# AFPGA_FMC2_bank2.net
KiCad netlist of a schematic drawn in Altium Designer
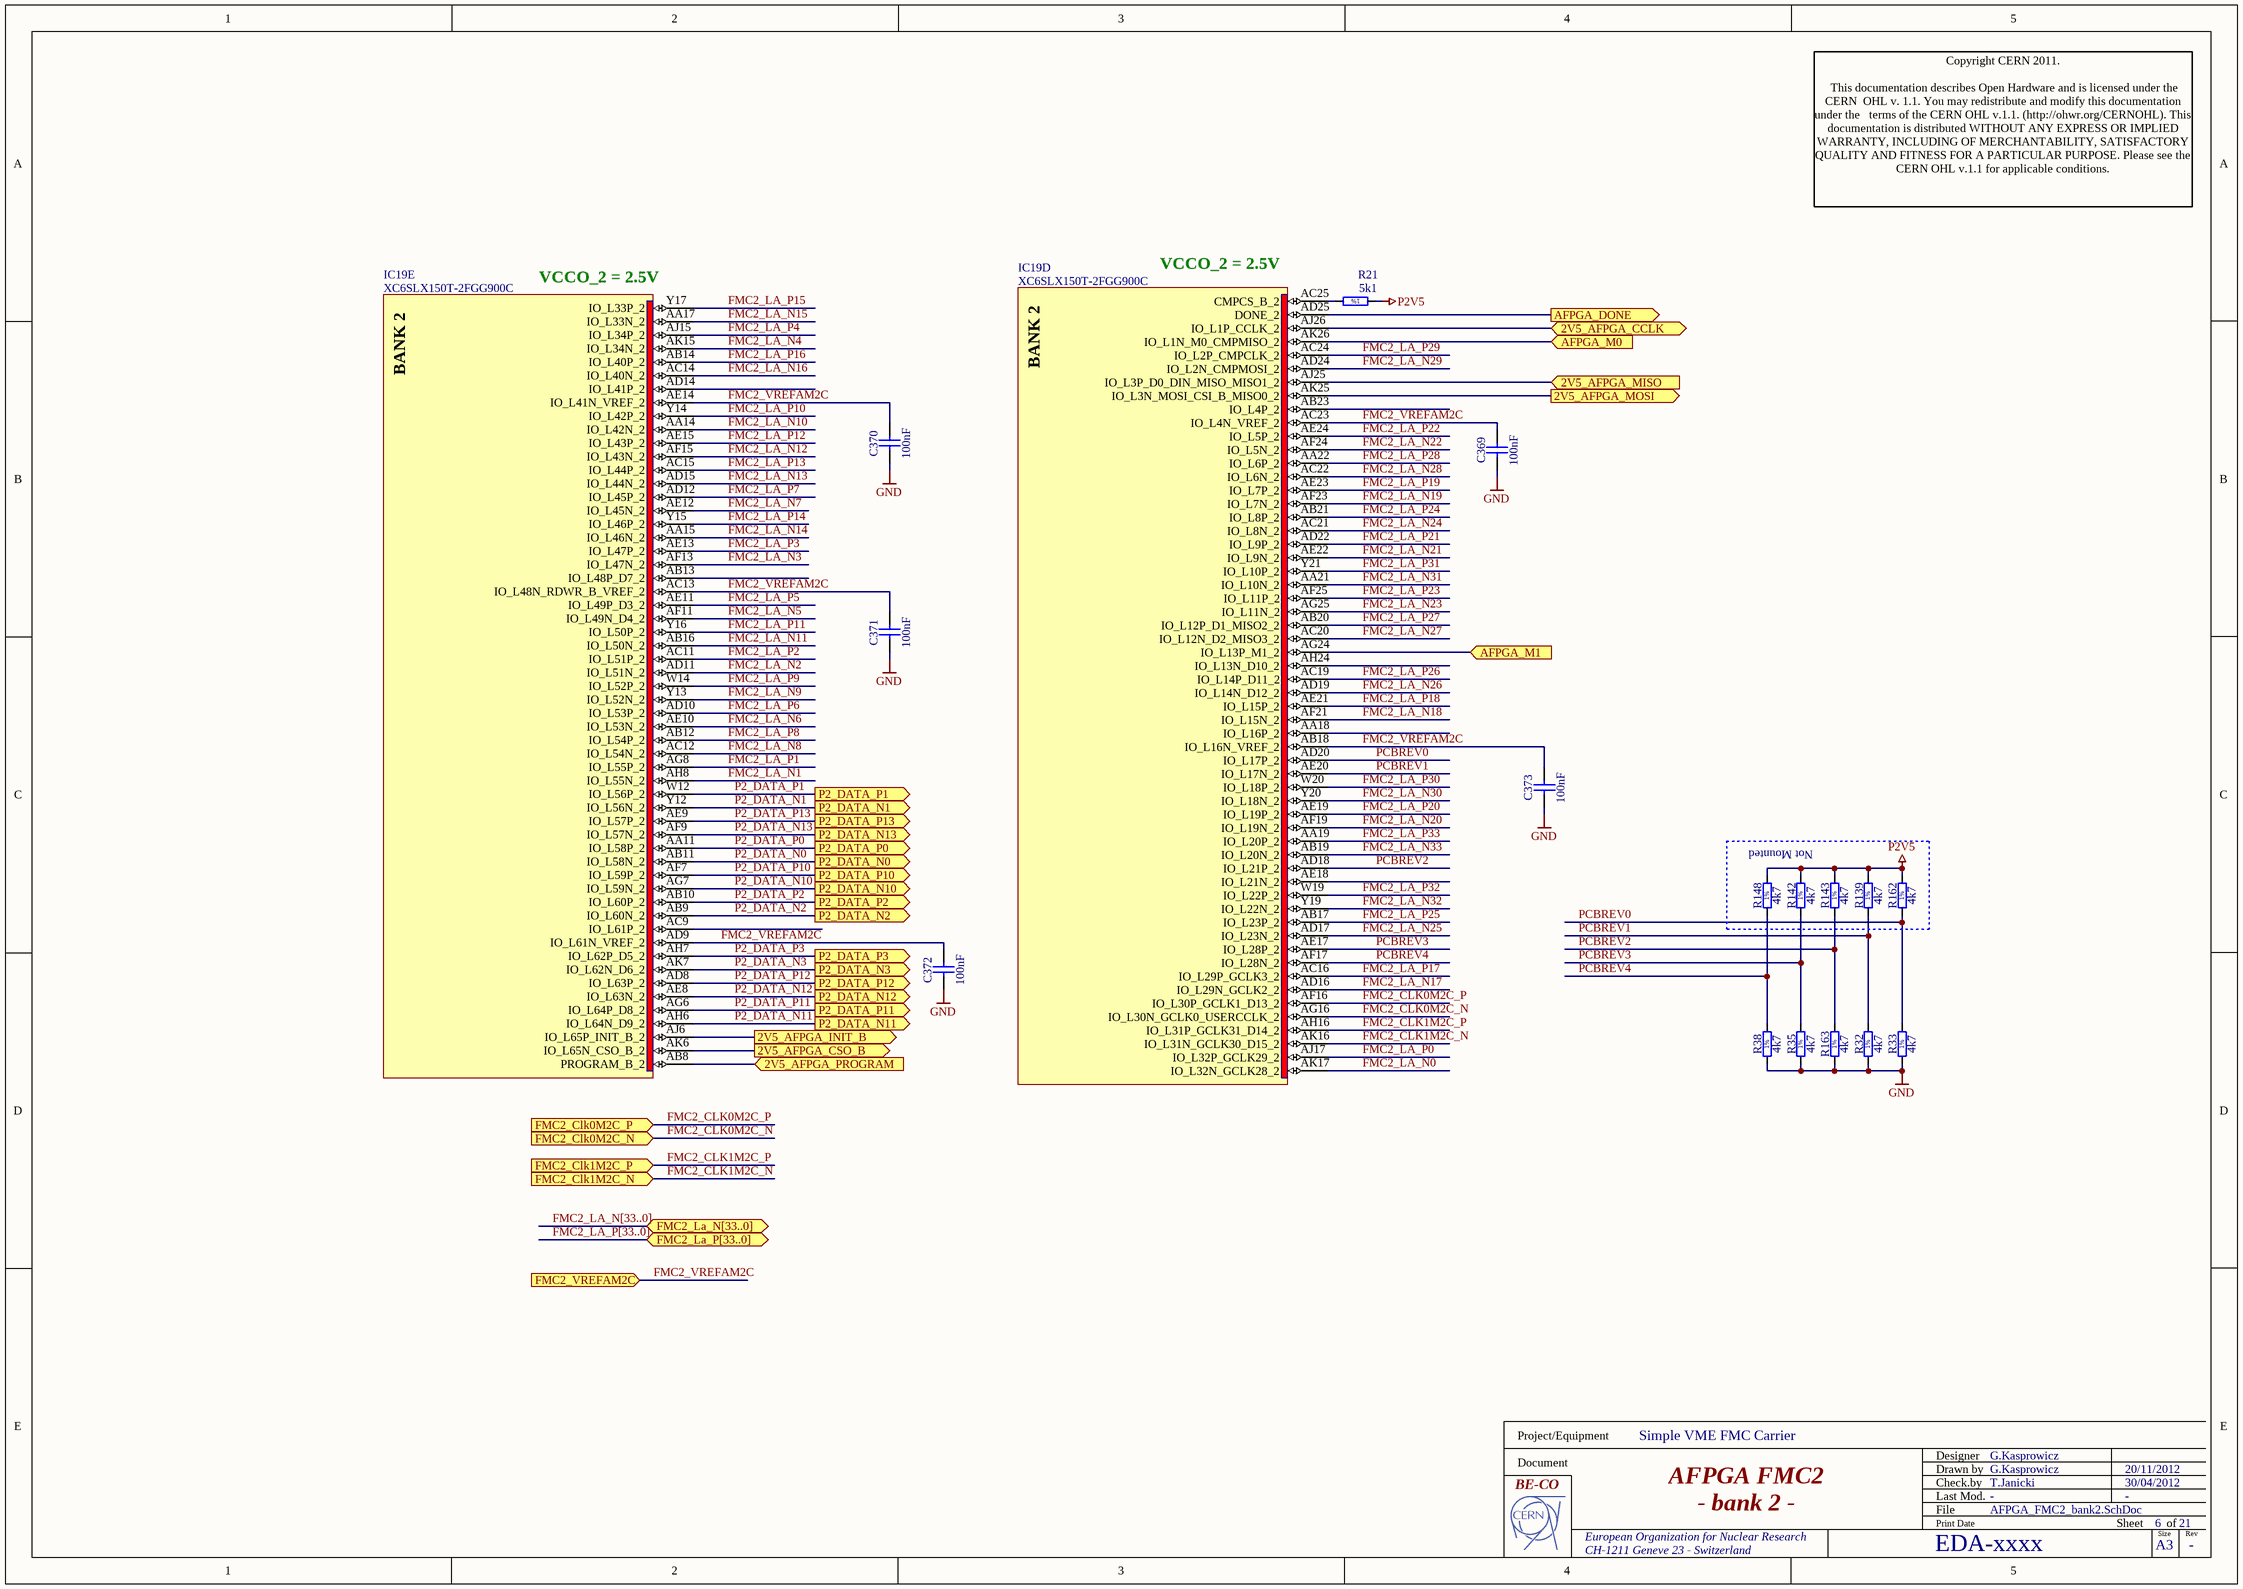
[diagram p0: AFPGA_FMC2_bank2.SchDoc]

(export (version "E")
  (design (tool "Eeschema 10.0.6"))
  (components
    (comp (ref "C369")
      (value "100nF")
      (footprint "CAPC1005X55N")
      (description "Non-polarised capacitor")
      (fields
        (field (name "PART NUMBER") "CC0402_100NF_16V_10%_X7R")
        (field (name "VOLTAGE") "16V")
        (field (name "AUTHOR") "CERN DEM JLC")
      )
      (libsource (lib "Capacitors") (part "Capacitor - non polarized"))
    )
    (comp (ref "C370")
      (value "100nF")
      (footprint "CAPC1005X55N")
      (description "Non-polarised capacitor")
      (fields
        (field (name "PART NUMBER") "CC0402_100NF_16V_10%_X7R")
        (field (name "VOLTAGE") "16V")
        (field (name "AUTHOR") "CERN DEM JLC")
      )
      (libsource (lib "Capacitors") (part "Capacitor - non polarized"))
    )
    (comp (ref "C371")
      (value "100nF")
      (footprint "CAPC1005X55N")
      (description "Non-polarised capacitor")
      (fields
        (field (name "PART NUMBER") "CC0402_100NF_16V_10%_X7R")
        (field (name "VOLTAGE") "16V")
        (field (name "AUTHOR") "CERN DEM JLC")
      )
      (libsource (lib "Capacitors") (part "Capacitor - non polarized"))
    )
    (comp (ref "C372")
      (value "100nF")
      (footprint "CAPC1005X55N")
      (description "Non-polarised capacitor")
      (fields
        (field (name "PART NUMBER") "CC0402_100NF_16V_10%_X7R")
        (field (name "VOLTAGE") "16V")
        (field (name "AUTHOR") "CERN DEM JLC")
      )
      (libsource (lib "Capacitors") (part "Capacitor - non polarized"))
    )
    (comp (ref "C373")
      (value "100nF")
      (footprint "CAPC1005X55N")
      (description "Non-polarised capacitor")
      (fields
        (field (name "PART NUMBER") "CC0402_100NF_16V_10%_X7R")
        (field (name "VOLTAGE") "16V")
        (field (name "AUTHOR") "CERN DEM JLC")
      )
      (libsource (lib "Capacitors") (part "Capacitor - non polarized"))
    )
    (comp (ref "IC19")
      (value "XC6SLX150T-2FGG900C")
      (footprint "BGA900C100P30X30_3100X3100X260")
      (description "SPARTAN-6, FPGA, 900-Ball BGA, Commercial Grade, Pb-Free")
      (fields (field (name "MANUFACTURER") "XILINX") (field (name "AUTHOR") "CERN DEM JLC"))
      (libsource (lib "ICs And Semiconductors") (part "XC6SLX150T-2FGG900C"))
    )
    (comp (ref "R21")
      (value "5k1")
      (footprint "RESC1608X55N")
      (description "Resistor - 1%")
      (fields
        (field (name "PART NUMBER") "R0603_5K1_1%_0.1W_100PPM")
        (field (name "POWER") "0.1W")
        (field (name "AUTHOR") "CERN DEM JLC")
      )
      (libsource (lib "Resistors") (part "Resistor - 1%"))
    )
    (comp (ref "R32")
      (value "4k7")
      (footprint "RESC1608X55N")
      (description "Resistor - 1%")
      (fields
        (field (name "PART NUMBER") "R0603_4K7_1%_0.1W_100PPM")
        (field (name "POWER") "0.1W")
        (field (name "AUTHOR") "CERN DEM JLC")
      )
      (libsource (lib "Resistors") (part "Resistor - 1%"))
    )
    (comp (ref "R33")
      (value "4k7")
      (footprint "RESC1608X55N")
      (description "Resistor - 1%")
      (fields
        (field (name "PART NUMBER") "R0603_4K7_1%_0.1W_100PPM")
        (field (name "POWER") "0.1W")
        (field (name "AUTHOR") "CERN DEM JLC")
      )
      (libsource (lib "Resistors") (part "Resistor - 1%"))
    )
    (comp (ref "R35")
      (value "4k7")
      (footprint "RESC1608X55N")
      (description "Resistor - 1%")
      (fields
        (field (name "PART NUMBER") "R0603_4K7_1%_0.1W_100PPM")
        (field (name "POWER") "0.1W")
        (field (name "AUTHOR") "CERN DEM JLC")
      )
      (libsource (lib "Resistors") (part "Resistor - 1%"))
    )
    (comp (ref "R38")
      (value "4k7")
      (footprint "RESC1608X55N")
      (description "Resistor - 1%")
      (fields
        (field (name "PART NUMBER") "R0603_4K7_1%_0.1W_100PPM")
        (field (name "POWER") "0.1W")
        (field (name "AUTHOR") "CERN DEM JLC")
      )
      (libsource (lib "Resistors") (part "Resistor - 1%"))
    )
    (comp (ref "R139")
      (value "4k7")
      (footprint "RESC1608X55N")
      (description "Resistor - 1%")
      (fields
        (field (name "PART NUMBER") "R0603_4K7_1%_0.1W_100PPM")
        (field (name "POWER") "0.1W")
        (field (name "AUTHOR") "CERN DEM JLC")
      )
      (libsource (lib "Resistors") (part "Resistor - 1%"))
    )
    (comp (ref "R142")
      (value "4k7")
      (footprint "RESC1608X55N")
      (description "Resistor - 1%")
      (fields
        (field (name "PART NUMBER") "R0603_4K7_1%_0.1W_100PPM")
        (field (name "POWER") "0.1W")
        (field (name "AUTHOR") "CERN DEM JLC")
      )
      (libsource (lib "Resistors") (part "Resistor - 1%"))
    )
    (comp (ref "R143")
      (value "4k7")
      (footprint "RESC1608X55N")
      (description "Resistor - 1%")
      (fields
        (field (name "PART NUMBER") "R0603_4K7_1%_0.1W_100PPM")
        (field (name "POWER") "0.1W")
        (field (name "AUTHOR") "CERN DEM JLC")
      )
      (libsource (lib "Resistors") (part "Resistor - 1%"))
    )
    (comp (ref "R148")
      (value "4k7")
      (footprint "RESC1608X55N")
      (description "Resistor - 1%")
      (fields
        (field (name "PART NUMBER") "R0603_4K7_1%_0.1W_100PPM")
        (field (name "POWER") "0.1W")
        (field (name "AUTHOR") "CERN DEM JLC")
      )
      (libsource (lib "Resistors") (part "Resistor - 1%"))
    )
    (comp (ref "R162")
      (value "4k7")
      (footprint "RESC1608X55N")
      (description "Resistor - 1%")
      (fields
        (field (name "PART NUMBER") "R0603_4K7_1%_0.1W_100PPM")
        (field (name "POWER") "0.1W")
        (field (name "AUTHOR") "CERN DEM JLC")
      )
      (libsource (lib "Resistors") (part "Resistor - 1%"))
    )
    (comp (ref "R163")
      (value "4k7")
      (footprint "RESC1608X55N")
      (description "Resistor - 1%")
      (fields
        (field (name "PART NUMBER") "R0603_4K7_1%_0.1W_100PPM")
        (field (name "POWER") "0.1W")
        (field (name "AUTHOR") "CERN DEM JLC")
      )
      (libsource (lib "Resistors") (part "Resistor - 1%"))
    )
  )
  (nets
    (net (code "1") (name "/2V5_AFPGA_CCLK") (class "Default")
      (node (ref "IC19") (pin "AJ26") (pinfunction "IO_L1P_CCLK_2_AJ26") (pintype "bidirectional"))
    )
    (net (code "2") (name "/2V5_AFPGA_CSO_B") (class "Default")
      (node (ref "IC19") (pin "AK6") (pinfunction "IO_L65N_CSO_B_2_AK6") (pintype "bidirectional"))
    )
    (net (code "3") (name "/2V5_AFPGA_INIT_B") (class "Default")
      (node (ref "IC19") (pin "AJ6") (pinfunction "IO_L65P_INIT_B_2_AJ6") (pintype "bidirectional"))
    )
    (net (code "4") (name "/2V5_AFPGA_MISO") (class "Default")
      (node (ref "IC19") (pin "AJ25") (pinfunction "IO_L3P_D0_DIN_MISO_MISO1_2_AJ25") (pintype "bidirectional"))
    )
    (net (code "5") (name "/2V5_AFPGA_MOSI") (class "Default")
      (node (ref "IC19") (pin "AK25") (pinfunction "IO_L3N_MOSI_CSI_B_MISO0_2_AK25") (pintype "bidirectional"))
    )
    (net (code "6") (name "/2V5_AFPGA_PROGRAM") (class "Default")
      (node (ref "IC19") (pin "AB8") (pinfunction "PROGRAM_B_2_AB8") (pintype "bidirectional"))
    )
    (net (code "7") (name "/AFPGA_DONE") (class "Default")
      (node (ref "IC19") (pin "AD25") (pinfunction "DONE_2_AD25") (pintype "bidirectional"))
    )
    (net (code "8") (name "/AFPGA_M0") (class "Default")
      (node (ref "IC19") (pin "AK26") (pinfunction "IO_L1N_M0_CMPMISO_2_AK26") (pintype "bidirectional"))
    )
    (net (code "9") (name "/AFPGA_M1") (class "Default")
      (node (ref "IC19") (pin "AG24") (pinfunction "IO_L13P_M1_2_AG24") (pintype "bidirectional"))
    )
    (net (code "10") (name "/FMC2_CLK0M2C_N") (class "Default")
      (node (ref "IC19") (pin "AG16") (pinfunction "IO_L30N_GCLK0_USERCCLK_2_AG16") (pintype "bidirectional"))
    )
    (net (code "11") (name "/FMC2_CLK0M2C_P") (class "Default")
      (node (ref "IC19") (pin "AF16") (pinfunction "IO_L30P_GCLK1_D13_2_AF16") (pintype "bidirectional"))
    )
    (net (code "12") (name "/FMC2_CLK1M2C_N") (class "Default")
      (node (ref "IC19") (pin "AK16") (pinfunction "IO_L31N_GCLK30_D15_2_AK16") (pintype "bidirectional"))
    )
    (net (code "13") (name "/FMC2_CLK1M2C_P") (class "Default")
      (node (ref "IC19") (pin "AH16") (pinfunction "IO_L31P_GCLK31_D14_2_AH16") (pintype "bidirectional"))
    )
    (net (code "14") (name "/FMC2_LA_N0") (class "Default")
      (node (ref "IC19") (pin "AK17") (pinfunction "IO_L32N_GCLK28_2_AK17") (pintype "bidirectional"))
    )
    (net (code "15") (name "/FMC2_LA_N1") (class "Default")
      (node (ref "IC19") (pin "AH8") (pinfunction "IO_L55N_2_AH8") (pintype "bidirectional"))
    )
    (net (code "16") (name "/FMC2_LA_N2") (class "Default")
      (node (ref "IC19") (pin "AD11") (pinfunction "IO_L51N_2_AD11") (pintype "bidirectional"))
    )
    (net (code "17") (name "/FMC2_LA_N3") (class "Default")
      (node (ref "IC19") (pin "AF13") (pinfunction "IO_L47N_2_AF13") (pintype "bidirectional"))
    )
    (net (code "18") (name "/FMC2_LA_N4") (class "Default")
      (node (ref "IC19") (pin "AK15") (pinfunction "IO_L34N_2_AK15") (pintype "bidirectional"))
    )
    (net (code "19") (name "/FMC2_LA_N5") (class "Default")
      (node (ref "IC19") (pin "AF11") (pinfunction "IO_L49N_D4_2_AF11") (pintype "bidirectional"))
    )
    (net (code "20") (name "/FMC2_LA_N6") (class "Default")
      (node (ref "IC19") (pin "AE10") (pinfunction "IO_L53N_2_AE10") (pintype "bidirectional"))
    )
    (net (code "21") (name "/FMC2_LA_N7") (class "Default")
      (node (ref "IC19") (pin "AE12") (pinfunction "IO_L45N_2_AE12") (pintype "bidirectional"))
    )
    (net (code "22") (name "/FMC2_LA_N8") (class "Default")
      (node (ref "IC19") (pin "AC12") (pinfunction "IO_L54N_2_AC12") (pintype "bidirectional"))
    )
    (net (code "23") (name "/FMC2_LA_N9") (class "Default")
      (node (ref "IC19") (pin "Y13") (pinfunction "IO_L52N_2_Y13") (pintype "bidirectional"))
    )
    (net (code "24") (name "/FMC2_LA_N10") (class "Default")
      (node (ref "IC19") (pin "AA14") (pinfunction "IO_L42N_2_AA14") (pintype "bidirectional"))
    )
    (net (code "25") (name "/FMC2_LA_N11") (class "Default")
      (node (ref "IC19") (pin "AB16") (pinfunction "IO_L50N_2_AB16") (pintype "bidirectional"))
    )
    (net (code "26") (name "/FMC2_LA_N12") (class "Default")
      (node (ref "IC19") (pin "AF15") (pinfunction "IO_L43N_2_AF15") (pintype "bidirectional"))
    )
    (net (code "27") (name "/FMC2_LA_N13") (class "Default")
      (node (ref "IC19") (pin "AD15") (pinfunction "IO_L44N_2_AD15") (pintype "bidirectional"))
    )
    (net (code "28") (name "/FMC2_LA_N14") (class "Default")
      (node (ref "IC19") (pin "AA15") (pinfunction "IO_L46N_2_AA15") (pintype "bidirectional"))
    )
    (net (code "29") (name "/FMC2_LA_N15") (class "Default")
      (node (ref "IC19") (pin "AA17") (pinfunction "IO_L33N_2_AA17") (pintype "bidirectional"))
    )
    (net (code "30") (name "/FMC2_LA_N16") (class "Default")
      (node (ref "IC19") (pin "AC14") (pinfunction "IO_L40N_2_AC14") (pintype "bidirectional"))
    )
    (net (code "31") (name "/FMC2_LA_N17") (class "Default")
      (node (ref "IC19") (pin "AD16") (pinfunction "IO_L29N_GCLK2_2_AD16") (pintype "bidirectional"))
    )
    (net (code "32") (name "/FMC2_LA_N18") (class "Default")
      (node (ref "IC19") (pin "AF21") (pinfunction "IO_L15N_2_AF21") (pintype "bidirectional"))
    )
    (net (code "33") (name "/FMC2_LA_N19") (class "Default")
      (node (ref "IC19") (pin "AF23") (pinfunction "IO_L7N_2_AF23") (pintype "bidirectional"))
    )
    (net (code "34") (name "/FMC2_LA_N20") (class "Default")
      (node (ref "IC19") (pin "AF19") (pinfunction "IO_L19N_2_AF19") (pintype "bidirectional"))
    )
    (net (code "35") (name "/FMC2_LA_N21") (class "Default")
      (node (ref "IC19") (pin "AE22") (pinfunction "IO_L9N_2_AE22") (pintype "bidirectional"))
    )
    (net (code "36") (name "/FMC2_LA_N22") (class "Default")
      (node (ref "IC19") (pin "AF24") (pinfunction "IO_L5N_2_AF24") (pintype "bidirectional"))
    )
    (net (code "37") (name "/FMC2_LA_N23") (class "Default")
      (node (ref "IC19") (pin "AG25") (pinfunction "IO_L11N_2_AG25") (pintype "bidirectional"))
    )
    (net (code "38") (name "/FMC2_LA_N24") (class "Default")
      (node (ref "IC19") (pin "AC21") (pinfunction "IO_L8N_2_AC21") (pintype "bidirectional"))
    )
    (net (code "39") (name "/FMC2_LA_N25") (class "Default")
      (node (ref "IC19") (pin "AD17") (pinfunction "IO_L23N_2_AD17") (pintype "bidirectional"))
    )
    (net (code "40") (name "/FMC2_LA_N26") (class "Default")
      (node (ref "IC19") (pin "AD19") (pinfunction "IO_L14N_D12_2_AD19") (pintype "bidirectional"))
    )
    (net (code "41") (name "/FMC2_LA_N27") (class "Default")
      (node (ref "IC19") (pin "AC20") (pinfunction "IO_L12N_D2_MISO3_2_AC20") (pintype "bidirectional"))
    )
    (net (code "42") (name "/FMC2_LA_N28") (class "Default")
      (node (ref "IC19") (pin "AC22") (pinfunction "IO_L6N_2_AC22") (pintype "bidirectional"))
    )
    (net (code "43") (name "/FMC2_LA_N29") (class "Default")
      (node (ref "IC19") (pin "AD24") (pinfunction "IO_L2N_CMPMOSI_2_AD24") (pintype "bidirectional"))
    )
    (net (code "44") (name "/FMC2_LA_N30") (class "Default")
      (node (ref "IC19") (pin "Y20") (pinfunction "IO_L18N_2_Y20") (pintype "bidirectional"))
    )
    (net (code "45") (name "/FMC2_LA_N31") (class "Default")
      (node (ref "IC19") (pin "AA21") (pinfunction "IO_L10N_2_AA21") (pintype "bidirectional"))
    )
    (net (code "46") (name "/FMC2_LA_N32") (class "Default")
      (node (ref "IC19") (pin "Y19") (pinfunction "IO_L22N_2_Y19") (pintype "bidirectional"))
    )
    (net (code "47") (name "/FMC2_LA_N33") (class "Default")
      (node (ref "IC19") (pin "AB19") (pinfunction "IO_L20N_2_AB19") (pintype "bidirectional"))
    )
    (net (code "49") (name "/FMC2_LA_P0") (class "Default")
      (node (ref "IC19") (pin "AJ17") (pinfunction "IO_L32P_GCLK29_2_AJ17") (pintype "bidirectional"))
    )
    (net (code "50") (name "/FMC2_LA_P1") (class "Default")
      (node (ref "IC19") (pin "AG8") (pinfunction "IO_L55P_2_AG8") (pintype "bidirectional"))
    )
    (net (code "51") (name "/FMC2_LA_P2") (class "Default")
      (node (ref "IC19") (pin "AC11") (pinfunction "IO_L51P_2_AC11") (pintype "bidirectional"))
    )
    (net (code "52") (name "/FMC2_LA_P3") (class "Default")
      (node (ref "IC19") (pin "AE13") (pinfunction "IO_L47P_2_AE13") (pintype "bidirectional"))
    )
    (net (code "53") (name "/FMC2_LA_P4") (class "Default")
      (node (ref "IC19") (pin "AJ15") (pinfunction "IO_L34P_2_AJ15") (pintype "bidirectional"))
    )
    (net (code "54") (name "/FMC2_LA_P5") (class "Default")
      (node (ref "IC19") (pin "AE11") (pinfunction "IO_L49P_D3_2_AE11") (pintype "bidirectional"))
    )
    (net (code "55") (name "/FMC2_LA_P6") (class "Default")
      (node (ref "IC19") (pin "AD10") (pinfunction "IO_L53P_2_AD10") (pintype "bidirectional"))
    )
    (net (code "56") (name "/FMC2_LA_P7") (class "Default")
      (node (ref "IC19") (pin "AD12") (pinfunction "IO_L45P_2_AD12") (pintype "bidirectional"))
    )
    (net (code "57") (name "/FMC2_LA_P8") (class "Default")
      (node (ref "IC19") (pin "AB12") (pinfunction "IO_L54P_2_AB12") (pintype "bidirectional"))
    )
    (net (code "58") (name "/FMC2_LA_P9") (class "Default")
      (node (ref "IC19") (pin "W14") (pinfunction "IO_L52P_2_W14") (pintype "bidirectional"))
    )
    (net (code "59") (name "/FMC2_LA_P10") (class "Default")
      (node (ref "IC19") (pin "Y14") (pinfunction "IO_L42P_2_Y14") (pintype "bidirectional"))
    )
    (net (code "60") (name "/FMC2_LA_P11") (class "Default")
      (node (ref "IC19") (pin "Y16") (pinfunction "IO_L50P_2_Y16") (pintype "bidirectional"))
    )
    (net (code "61") (name "/FMC2_LA_P12") (class "Default")
      (node (ref "IC19") (pin "AE15") (pinfunction "IO_L43P_2_AE15") (pintype "bidirectional"))
    )
    (net (code "62") (name "/FMC2_LA_P13") (class "Default")
      (node (ref "IC19") (pin "AC15") (pinfunction "IO_L44P_2_AC15") (pintype "bidirectional"))
    )
    (net (code "63") (name "/FMC2_LA_P14") (class "Default")
      (node (ref "IC19") (pin "Y15") (pinfunction "IO_L46P_2_Y15") (pintype "bidirectional"))
    )
    (net (code "64") (name "/FMC2_LA_P15") (class "Default")
      (node (ref "IC19") (pin "Y17") (pinfunction "IO_L33P_2_Y17") (pintype "bidirectional"))
    )
    (net (code "65") (name "/FMC2_LA_P16") (class "Default")
      (node (ref "IC19") (pin "AB14") (pinfunction "IO_L40P_2_AB14") (pintype "bidirectional"))
    )
    (net (code "66") (name "/FMC2_LA_P17") (class "Default")
      (node (ref "IC19") (pin "AC16") (pinfunction "IO_L29P_GCLK3_2_AC16") (pintype "bidirectional"))
    )
    (net (code "67") (name "/FMC2_LA_P18") (class "Default")
      (node (ref "IC19") (pin "AE21") (pinfunction "IO_L15P_2_AE21") (pintype "bidirectional"))
    )
    (net (code "68") (name "/FMC2_LA_P19") (class "Default")
      (node (ref "IC19") (pin "AE23") (pinfunction "IO_L7P_2_AE23") (pintype "bidirectional"))
    )
    (net (code "69") (name "/FMC2_LA_P20") (class "Default")
      (node (ref "IC19") (pin "AE19") (pinfunction "IO_L19P_2_AE19") (pintype "bidirectional"))
    )
    (net (code "70") (name "/FMC2_LA_P21") (class "Default")
      (node (ref "IC19") (pin "AD22") (pinfunction "IO_L9P_2_AD22") (pintype "bidirectional"))
    )
    (net (code "71") (name "/FMC2_LA_P22") (class "Default")
      (node (ref "IC19") (pin "AE24") (pinfunction "IO_L5P_2_AE24") (pintype "bidirectional"))
    )
    (net (code "72") (name "/FMC2_LA_P23") (class "Default")
      (node (ref "IC19") (pin "AF25") (pinfunction "IO_L11P_2_AF25") (pintype "bidirectional"))
    )
    (net (code "73") (name "/FMC2_LA_P24") (class "Default")
      (node (ref "IC19") (pin "AB21") (pinfunction "IO_L8P_2_AB21") (pintype "bidirectional"))
    )
    (net (code "74") (name "/FMC2_LA_P25") (class "Default")
      (node (ref "IC19") (pin "AB17") (pinfunction "IO_L23P_2_AB17") (pintype "bidirectional"))
    )
    (net (code "75") (name "/FMC2_LA_P26") (class "Default")
      (node (ref "IC19") (pin "AC19") (pinfunction "IO_L14P_D11_2_AC19") (pintype "bidirectional"))
    )
    (net (code "76") (name "/FMC2_LA_P27") (class "Default")
      (node (ref "IC19") (pin "AB20") (pinfunction "IO_L12P_D1_MISO2_2_AB20") (pintype "bidirectional"))
    )
    (net (code "77") (name "/FMC2_LA_P28") (class "Default")
      (node (ref "IC19") (pin "AA22") (pinfunction "IO_L6P_2_AA22") (pintype "bidirectional"))
    )
    (net (code "78") (name "/FMC2_LA_P29") (class "Default")
      (node (ref "IC19") (pin "AC24") (pinfunction "IO_L2P_CMPCLK_2_AC24") (pintype "bidirectional"))
    )
    (net (code "79") (name "/FMC2_LA_P30") (class "Default")
      (node (ref "IC19") (pin "W20") (pinfunction "IO_L18P_2_W20") (pintype "bidirectional"))
    )
    (net (code "80") (name "/FMC2_LA_P31") (class "Default")
      (node (ref "IC19") (pin "Y21") (pinfunction "IO_L10P_2_Y21") (pintype "bidirectional"))
    )
    (net (code "81") (name "/FMC2_LA_P32") (class "Default")
      (node (ref "IC19") (pin "W19") (pinfunction "IO_L22P_2_W19") (pintype "bidirectional"))
    )
    (net (code "82") (name "/FMC2_LA_P33") (class "Default")
      (node (ref "IC19") (pin "AA19") (pinfunction "IO_L20P_2_AA19") (pintype "bidirectional"))
    )
    (net (code "84") (name "/FMC2_VREFAM2C") (class "Default")
      (node (ref "C369") (pin "2") (pinfunction "2_2") (pintype "passive"))
      (node (ref "C370") (pin "2") (pinfunction "2_2") (pintype "passive"))
      (node (ref "C371") (pin "2") (pinfunction "2_2") (pintype "passive"))
      (node (ref "C372") (pin "2") (pinfunction "2_2") (pintype "passive"))
      (node (ref "C373") (pin "2") (pinfunction "2_2") (pintype "passive"))
      (node (ref "IC19") (pin "AB18") (pinfunction "IO_L16N_VREF_2_AB18") (pintype "bidirectional"))
      (node (ref "IC19") (pin "AC13") (pinfunction "IO_L48N_RDWR_B_VREF_2_AC13") (pintype "bidirectional"))
      (node (ref "IC19") (pin "AC23") (pinfunction "IO_L4N_VREF_2_AC23") (pintype "bidirectional"))
      (node (ref "IC19") (pin "AD9") (pinfunction "IO_L61N_VREF_2_AD9") (pintype "bidirectional"))
      (node (ref "IC19") (pin "AE14") (pinfunction "IO_L41N_VREF_2_AE14") (pintype "bidirectional"))
    )
    (net (code "85") (name "/P2_DATA_N0") (class "Default")
      (node (ref "IC19") (pin "AB11") (pinfunction "IO_L58N_2_AB11") (pintype "bidirectional"))
    )
    (net (code "86") (name "/P2_DATA_N1") (class "Default")
      (node (ref "IC19") (pin "Y12") (pinfunction "IO_L56N_2_Y12") (pintype "bidirectional"))
    )
    (net (code "87") (name "/P2_DATA_N2") (class "Default")
      (node (ref "IC19") (pin "AB9") (pinfunction "IO_L60N_2_AB9") (pintype "bidirectional"))
    )
    (net (code "88") (name "/P2_DATA_N3") (class "Default")
      (node (ref "IC19") (pin "AK7") (pinfunction "IO_L62N_D6_2_AK7") (pintype "bidirectional"))
    )
    (net (code "89") (name "/P2_DATA_N10") (class "Default")
      (node (ref "IC19") (pin "AG7") (pinfunction "IO_L59N_2_AG7") (pintype "bidirectional"))
    )
    (net (code "90") (name "/P2_DATA_N11") (class "Default")
      (node (ref "IC19") (pin "AH6") (pinfunction "IO_L64N_D9_2_AH6") (pintype "bidirectional"))
    )
    (net (code "91") (name "/P2_DATA_N12") (class "Default")
      (node (ref "IC19") (pin "AE8") (pinfunction "IO_L63N_2_AE8") (pintype "bidirectional"))
    )
    (net (code "92") (name "/P2_DATA_N13") (class "Default")
      (node (ref "IC19") (pin "AF9") (pinfunction "IO_L57N_2_AF9") (pintype "bidirectional"))
    )
    (net (code "93") (name "/P2_DATA_P0") (class "Default")
      (node (ref "IC19") (pin "AA11") (pinfunction "IO_L58P_2_AA11") (pintype "bidirectional"))
    )
    (net (code "94") (name "/P2_DATA_P1") (class "Default")
      (node (ref "IC19") (pin "W12") (pinfunction "IO_L56P_2_W12") (pintype "bidirectional"))
    )
    (net (code "95") (name "/P2_DATA_P2") (class "Default")
      (node (ref "IC19") (pin "AB10") (pinfunction "IO_L60P_2_AB10") (pintype "bidirectional"))
    )
    (net (code "96") (name "/P2_DATA_P3") (class "Default")
      (node (ref "IC19") (pin "AH7") (pinfunction "IO_L62P_D5_2_AH7") (pintype "bidirectional"))
    )
    (net (code "97") (name "/P2_DATA_P10") (class "Default")
      (node (ref "IC19") (pin "AF7") (pinfunction "IO_L59P_2_AF7") (pintype "bidirectional"))
    )
    (net (code "98") (name "/P2_DATA_P11") (class "Default")
      (node (ref "IC19") (pin "AG6") (pinfunction "IO_L64P_D8_2_AG6") (pintype "bidirectional"))
    )
    (net (code "99") (name "/P2_DATA_P12") (class "Default")
      (node (ref "IC19") (pin "AD8") (pinfunction "IO_L63P_2_AD8") (pintype "bidirectional"))
    )
    (net (code "100") (name "/P2_DATA_P13") (class "Default")
      (node (ref "IC19") (pin "AE9") (pinfunction "IO_L57P_2_AE9") (pintype "bidirectional"))
    )
    (net (code "101") (name "/PCBREV0") (class "Default")
      (node (ref "IC19") (pin "AD20") (pinfunction "IO_L17P_2_AD20") (pintype "bidirectional"))
      (node (ref "R162") (pin "1") (pinfunction "1_1") (pintype "passive"))
      (node (ref "R33") (pin "2") (pinfunction "2_2") (pintype "passive"))
    )
    (net (code "102") (name "/PCBREV1") (class "Default")
      (node (ref "IC19") (pin "AE20") (pinfunction "IO_L17N_2_AE20") (pintype "bidirectional"))
      (node (ref "R139") (pin "1") (pinfunction "1_1") (pintype "passive"))
      (node (ref "R32") (pin "2") (pinfunction "2_2") (pintype "passive"))
    )
    (net (code "103") (name "/PCBREV2") (class "Default")
      (node (ref "IC19") (pin "AD18") (pinfunction "IO_L21P_2_AD18") (pintype "bidirectional"))
      (node (ref "R143") (pin "1") (pinfunction "1_1") (pintype "passive"))
      (node (ref "R163") (pin "2") (pinfunction "2_2") (pintype "passive"))
    )
    (net (code "104") (name "/PCBREV3") (class "Default")
      (node (ref "IC19") (pin "AE17") (pinfunction "IO_L28P_2_AE17") (pintype "bidirectional"))
      (node (ref "R142") (pin "1") (pinfunction "1_1") (pintype "passive"))
      (node (ref "R35") (pin "2") (pinfunction "2_2") (pintype "passive"))
    )
    (net (code "105") (name "/PCBREV4") (class "Default")
      (node (ref "IC19") (pin "AF17") (pinfunction "IO_L28N_2_AF17") (pintype "bidirectional"))
      (node (ref "R148") (pin "1") (pinfunction "1_1") (pintype "passive"))
      (node (ref "R38") (pin "2") (pinfunction "2_2") (pintype "passive"))
    )
    (net (code "106") (name "GND") (class "Default")
      (node (ref "C369") (pin "1") (pinfunction "1_1") (pintype "passive"))
      (node (ref "C370") (pin "1") (pinfunction "1_1") (pintype "passive"))
      (node (ref "C371") (pin "1") (pinfunction "1_1") (pintype "passive"))
      (node (ref "C372") (pin "1") (pinfunction "1_1") (pintype "passive"))
      (node (ref "C373") (pin "1") (pinfunction "1_1") (pintype "passive"))
      (node (ref "R163") (pin "1") (pinfunction "1_1") (pintype "passive"))
      (node (ref "R32") (pin "1") (pinfunction "1_1") (pintype "passive"))
      (node (ref "R33") (pin "1") (pinfunction "1_1") (pintype "passive"))
      (node (ref "R35") (pin "1") (pinfunction "1_1") (pintype "passive"))
      (node (ref "R38") (pin "1") (pinfunction "1_1") (pintype "passive"))
    )
    (net (code "107") (name "Net-(IC19D-CMPCS_B_2)") (class "Default")
      (node (ref "IC19") (pin "AC25") (pinfunction "CMPCS_B_2_AC25") (pintype "bidirectional"))
      (node (ref "R21") (pin "2") (pinfunction "2_2") (pintype "passive"))
    )
    (net (code "108") (name "P2V5") (class "Default")
      (node (ref "R139") (pin "2") (pinfunction "2_2") (pintype "passive"))
      (node (ref "R142") (pin "2") (pinfunction "2_2") (pintype "passive"))
      (node (ref "R143") (pin "2") (pinfunction "2_2") (pintype "passive"))
      (node (ref "R148") (pin "2") (pinfunction "2_2") (pintype "passive"))
      (node (ref "R162") (pin "2") (pinfunction "2_2") (pintype "passive"))
      (node (ref "R21") (pin "1") (pinfunction "1_1") (pintype "passive"))
    )
    (net (code "109") (name "unconnected-(IC19D-IO_L4P_2-PadAB23)") (class "Default")
      (node (ref "IC19") (pin "AB23") (pinfunction "IO_L4P_2_AB23") (pintype "bidirectional"))
    )
    (net (code "110") (name "unconnected-(IC19D-IO_L13N_D10_2-PadAH24)") (class "Default")
      (node (ref "IC19") (pin "AH24") (pinfunction "IO_L13N_D10_2_AH24") (pintype "bidirectional"))
    )
    (net (code "111") (name "unconnected-(IC19D-IO_L16P_2-PadAA18)") (class "Default")
      (node (ref "IC19") (pin "AA18") (pinfunction "IO_L16P_2_AA18") (pintype "bidirectional"))
    )
    (net (code "112") (name "unconnected-(IC19D-IO_L21N_2-PadAE18)") (class "Default")
      (node (ref "IC19") (pin "AE18") (pinfunction "IO_L21N_2_AE18") (pintype "bidirectional"))
    )
    (net (code "113") (name "unconnected-(IC19E-IO_L41P_2-PadAD14)") (class "Default")
      (node (ref "IC19") (pin "AD14") (pinfunction "IO_L41P_2_AD14") (pintype "bidirectional"))
    )
    (net (code "114") (name "unconnected-(IC19E-IO_L48P_D7_2-PadAB13)") (class "Default")
      (node (ref "IC19") (pin "AB13") (pinfunction "IO_L48P_D7_2_AB13") (pintype "bidirectional"))
    )
    (net (code "115") (name "unconnected-(IC19E-IO_L61P_2-PadAC9)") (class "Default")
      (node (ref "IC19") (pin "AC9") (pinfunction "IO_L61P_2_AC9") (pintype "bidirectional"))
    )
  )
)
